# Voicecard-SVF-v06.net
KiCad netlist of a schematic drawn in EAGLE
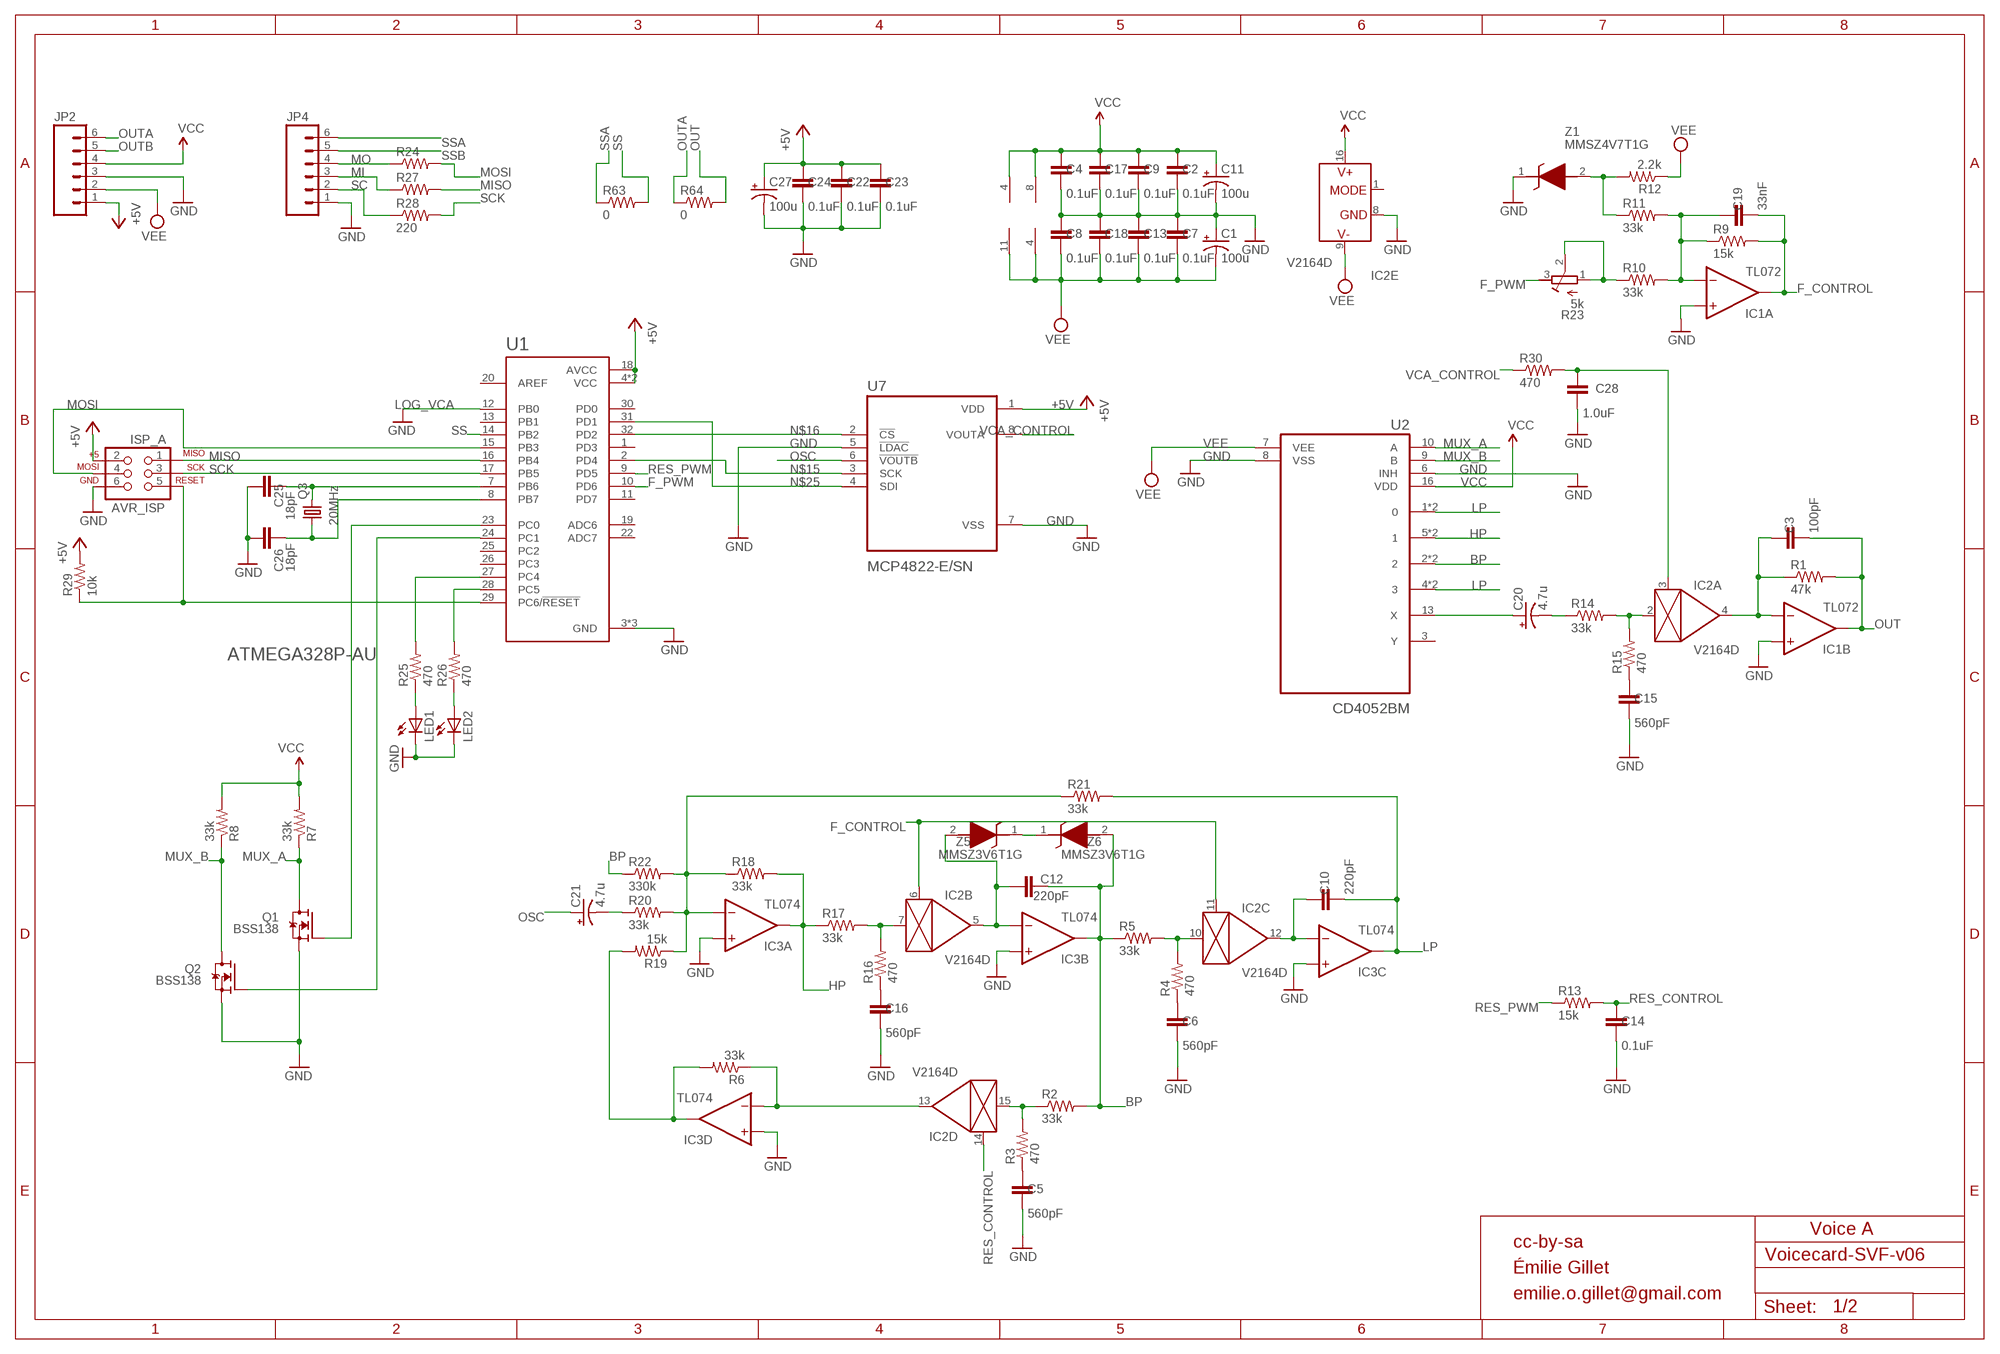
[diagram p0: schematic, sheet 1]
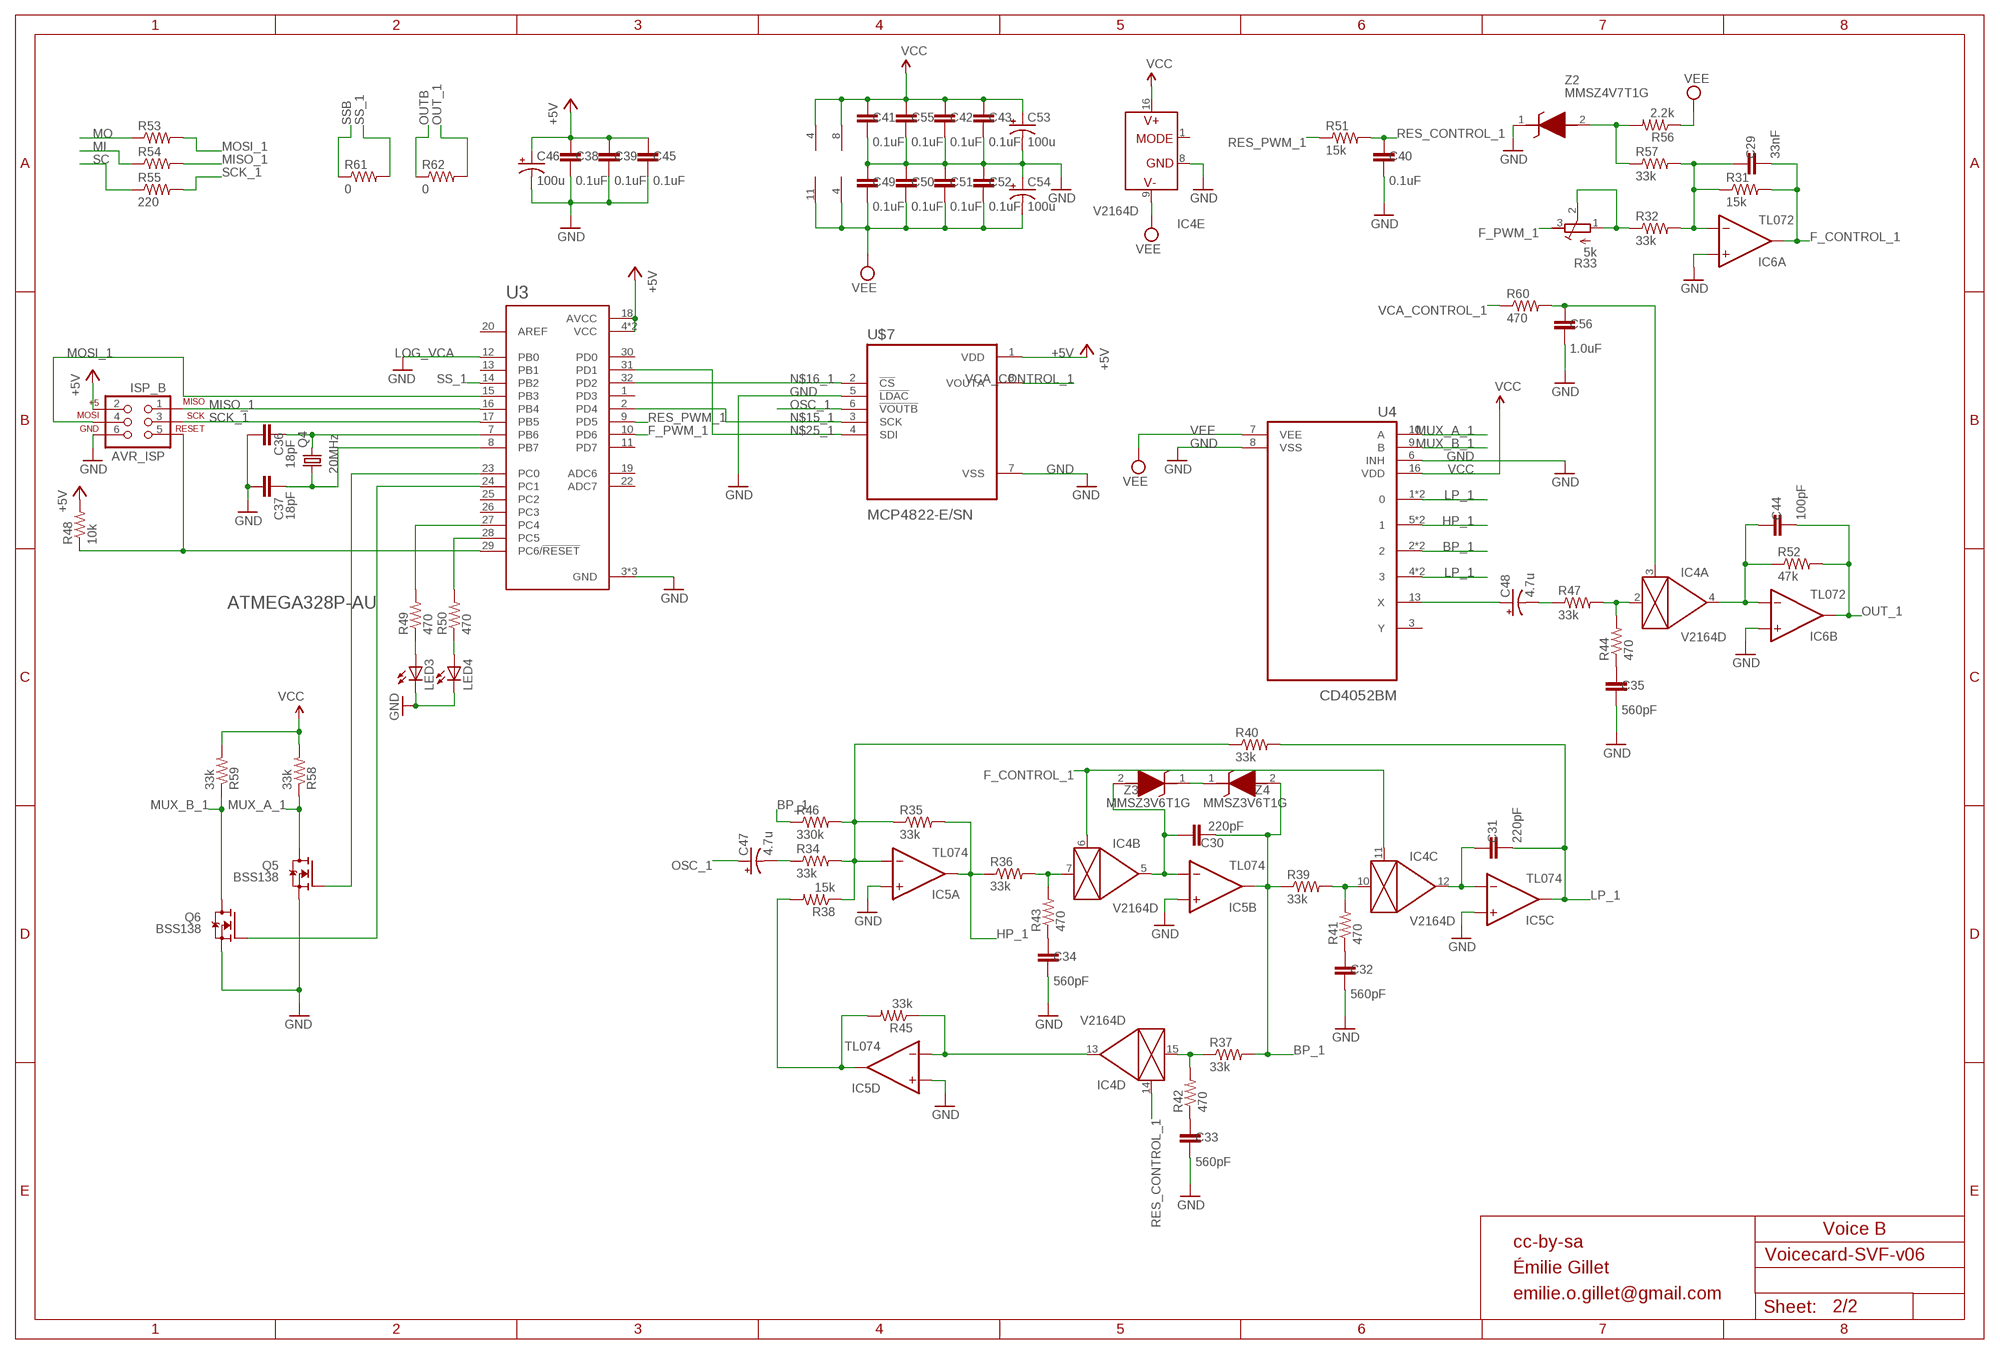
[diagram p1: schematic, sheet 2]

(export (version "E")
  (design (tool "Eeschema 10.0.6"))
  (components
    (comp (ref "C1")
      (value "100u")
      (footprint "eagle-import:PANASONIC_C")
      (libsource (lib "eagle-import") (part "CPOL-USC"))
    )
    (comp (ref "C2")
      (value "0.1uF")
      (footprint "eagle-import:0603")
      (libsource (lib "eagle-import") (part "0.1UF-0603-25V-5%"))
    )
    (comp (ref "C3")
      (value "100pF")
      (footprint "eagle-import:0603")
      (libsource (lib "eagle-import") (part "100PF-0603-50V-5%"))
    )
    (comp (ref "C4")
      (value "0.1uF")
      (footprint "eagle-import:0603")
      (libsource (lib "eagle-import") (part "0.1UF-0603-25V-5%"))
    )
    (comp (ref "C5")
      (value "560pF")
      (footprint "eagle-import:0603")
      (libsource (lib "eagle-import") (part "560PF-0603-50V-5%"))
    )
    (comp (ref "C6")
      (value "560pF")
      (footprint "eagle-import:0603")
      (libsource (lib "eagle-import") (part "560PF-0603-50V-5%"))
    )
    (comp (ref "C7")
      (value "0.1uF")
      (footprint "eagle-import:0603")
      (libsource (lib "eagle-import") (part "0.1UF-0603-25V-5%"))
    )
    (comp (ref "C8")
      (value "0.1uF")
      (footprint "eagle-import:0603")
      (libsource (lib "eagle-import") (part "0.1UF-0603-25V-5%"))
    )
    (comp (ref "C9")
      (value "0.1uF")
      (footprint "eagle-import:0603")
      (libsource (lib "eagle-import") (part "0.1UF-0603-25V-5%"))
    )
    (comp (ref "C10")
      (value "220pF")
      (footprint "eagle-import:0603")
      (libsource (lib "eagle-import") (part "270PF-0603-50V-5%"))
    )
    (comp (ref "C11")
      (value "100u")
      (footprint "eagle-import:PANASONIC_C")
      (libsource (lib "eagle-import") (part "CPOL-USC"))
    )
    (comp (ref "C12")
      (value "220pF")
      (footprint "eagle-import:0603")
      (libsource (lib "eagle-import") (part "270PF-0603-50V-5%"))
    )
    (comp (ref "C13")
      (value "0.1uF")
      (footprint "eagle-import:0603")
      (libsource (lib "eagle-import") (part "0.1UF-0603-25V-5%"))
    )
    (comp (ref "C14")
      (value "0.1uF")
      (footprint "eagle-import:0603")
      (libsource (lib "eagle-import") (part "0.1UF-0603-25V-5%"))
    )
    (comp (ref "C15")
      (value "560pF")
      (footprint "eagle-import:0603")
      (libsource (lib "eagle-import") (part "560PF-0603-50V-5%"))
    )
    (comp (ref "C16")
      (value "560pF")
      (footprint "eagle-import:0603")
      (libsource (lib "eagle-import") (part "560PF-0603-50V-5%"))
    )
    (comp (ref "C17")
      (value "0.1uF")
      (footprint "eagle-import:0603")
      (libsource (lib "eagle-import") (part "0.1UF-0603-25V-5%"))
    )
    (comp (ref "C18")
      (value "0.1uF")
      (footprint "eagle-import:0603")
      (libsource (lib "eagle-import") (part "0.1UF-0603-25V-5%"))
    )
    (comp (ref "C19")
      (value "33nF")
      (footprint "eagle-import:0603")
      (libsource (lib "eagle-import") (part "33NF-0603-50V-10%"))
    )
    (comp (ref "C20")
      (value "4.7u")
      (footprint "eagle-import:PANASONIC_A")
      (libsource (lib "eagle-import") (part "CPOL-USA"))
    )
    (comp (ref "C21")
      (value "4.7u")
      (footprint "eagle-import:PANASONIC_A")
      (libsource (lib "eagle-import") (part "CPOL-USA"))
    )
    (comp (ref "C22")
      (value "0.1uF")
      (footprint "eagle-import:0603")
      (libsource (lib "eagle-import") (part "0.1UF-0603-25V-5%"))
    )
    (comp (ref "C23")
      (value "0.1uF")
      (footprint "eagle-import:0603")
      (libsource (lib "eagle-import") (part "0.1UF-0603-25V-5%"))
    )
    (comp (ref "C24")
      (value "0.1uF")
      (footprint "eagle-import:0603")
      (libsource (lib "eagle-import") (part "0.1UF-0603-25V-5%"))
    )
    (comp (ref "C25")
      (value "18pF")
      (footprint "eagle-import:0603")
      (libsource (lib "eagle-import") (part "18PF-0603-50V-5%"))
    )
    (comp (ref "C26")
      (value "18pF")
      (footprint "eagle-import:0603")
      (libsource (lib "eagle-import") (part "18PF-0603-50V-5%"))
    )
    (comp (ref "C27")
      (value "100u")
      (footprint "eagle-import:PANASONIC_C")
      (libsource (lib "eagle-import") (part "CPOL-USC"))
    )
    (comp (ref "C28")
      (value "1.0uF")
      (footprint "eagle-import:0603")
      (libsource (lib "eagle-import") (part "1.0UF-0603-16V-10%"))
    )
    (comp (ref "IC1")
      (value "TL072")
      (footprint "eagle-import:SO08")
      (libsource (lib "eagle-import") (part "TL072_SMD"))
    )
    (comp (ref "IC2")
      (value "V2164D")
      (footprint "eagle-import:SOIC16N")
      (libsource (lib "eagle-import") (part "SSM2164S"))
    )
    (comp (ref "IC3")
      (value "TL074")
      (footprint "eagle-import:SO14")
      (libsource (lib "eagle-import") (part "TL074_SMD"))
    )
    (comp (ref "ISP_A")
      (value "AVR_ISP")
      (footprint "eagle-import:2X3")
      (libsource (lib "eagle-import") (part "AVR_SPI_PRG_6PTH"))
    )
    (comp (ref "JP2")
      (value "M06SIP")
      (footprint "eagle-import:1X06")
      (libsource (lib "eagle-import") (part "M06SIP"))
    )
    (comp (ref "JP4")
      (value "M06SIP")
      (footprint "eagle-import:1X06")
      (libsource (lib "eagle-import") (part "M06SIP"))
    )
    (comp (ref "LED1")
      (value "LED3MM")
      (footprint "eagle-import:LED3MM")
      (libsource (lib "eagle-import") (part "LED3MM"))
    )
    (comp (ref "LED2")
      (value "LED3MM")
      (footprint "eagle-import:LED3MM")
      (libsource (lib "eagle-import") (part "LED3MM"))
    )
    (comp (ref "Q1")
      (value "BSS138")
      (footprint "eagle-import:SOT95P240X111-3N")
      (fields (field (name "MF") "ON Semiconductor"))
      (libsource (lib "eagle-import") (part "BSS138"))
    )
    (comp (ref "Q2")
      (value "BSS138")
      (footprint "eagle-import:SOT95P240X111-3N")
      (fields (field (name "MF") "ON Semiconductor"))
      (libsource (lib "eagle-import") (part "BSS138"))
    )
    (comp (ref "Q3")
      (value "20MHz")
      (footprint "eagle-import:HC49UP")
      (libsource (lib "eagle-import") (part "CRYSTALHC49UP"))
    )
    (comp (ref "R1")
      (value "47k")
      (footprint "eagle-import:0603")
      (libsource (lib "eagle-import") (part "47KOHM-0603-1/10W-1%"))
    )
    (comp (ref "R2")
      (value "33k")
      (footprint "eagle-import:0603")
      (libsource (lib "eagle-import") (part "33KOHM-0603-1/10W-1%"))
    )
    (comp (ref "R3")
      (value "470")
      (footprint "eagle-import:0603")
      (libsource (lib "eagle-import") (part "470OHM-0603-1/10W-1%"))
    )
    (comp (ref "R4")
      (value "470")
      (footprint "eagle-import:0603")
      (libsource (lib "eagle-import") (part "470OHM-0603-1/10W-1%"))
    )
    (comp (ref "R5")
      (value "33k")
      (footprint "eagle-import:0603")
      (libsource (lib "eagle-import") (part "33KOHM-0603-1/10W-1%"))
    )
    (comp (ref "R6")
      (value "33k")
      (footprint "eagle-import:0603")
      (libsource (lib "eagle-import") (part "33KOHM-0603-1/10W-1%"))
    )
    (comp (ref "R7")
      (value "33k")
      (footprint "eagle-import:0603")
      (libsource (lib "eagle-import") (part "33KOHM-0603-1/10W-1%"))
    )
    (comp (ref "R8")
      (value "33k")
      (footprint "eagle-import:0603")
      (libsource (lib "eagle-import") (part "33KOHM-0603-1/10W-1%"))
    )
    (comp (ref "R9")
      (value "15k")
      (footprint "eagle-import:0603")
      (libsource (lib "eagle-import") (part "15KOHM-0603-1/10W-1%"))
    )
    (comp (ref "R10")
      (value "33k")
      (footprint "eagle-import:0603")
      (libsource (lib "eagle-import") (part "33KOHM-0603-1/10W-1%"))
    )
    (comp (ref "R11")
      (value "33k")
      (footprint "eagle-import:0603")
      (libsource (lib "eagle-import") (part "33KOHM-0603-1/10W-1%"))
    )
    (comp (ref "R12")
      (value "2.2k")
      (footprint "eagle-import:0603")
      (libsource (lib "eagle-import") (part "2.2KOHM-0603-1/10W-1%"))
    )
    (comp (ref "R13")
      (value "15k")
      (footprint "eagle-import:0603")
      (libsource (lib "eagle-import") (part "15KOHM-0603-1/10W-1%"))
    )
    (comp (ref "R14")
      (value "33k")
      (footprint "eagle-import:0603")
      (libsource (lib "eagle-import") (part "33KOHM-0603-1/10W-1%"))
    )
    (comp (ref "R15")
      (value "470")
      (footprint "eagle-import:0603")
      (libsource (lib "eagle-import") (part "470OHM-0603-1/10W-1%"))
    )
    (comp (ref "R16")
      (value "470")
      (footprint "eagle-import:0603")
      (libsource (lib "eagle-import") (part "470OHM-0603-1/10W-1%"))
    )
    (comp (ref "R17")
      (value "33k")
      (footprint "eagle-import:0603")
      (libsource (lib "eagle-import") (part "33KOHM-0603-1/10W-1%"))
    )
    (comp (ref "R18")
      (value "33k")
      (footprint "eagle-import:0603")
      (libsource (lib "eagle-import") (part "33KOHM-0603-1/10W-1%"))
    )
    (comp (ref "R19")
      (value "15k")
      (footprint "eagle-import:0603")
      (libsource (lib "eagle-import") (part "15KOHM-0603-1/10W-1%"))
    )
    (comp (ref "R20")
      (value "33k")
      (footprint "eagle-import:0603")
      (libsource (lib "eagle-import") (part "33KOHM-0603-1/10W-1%"))
    )
    (comp (ref "R21")
      (value "33k")
      (footprint "eagle-import:0603")
      (libsource (lib "eagle-import") (part "33KOHM-0603-1/10W-1%"))
    )
    (comp (ref "R22")
      (value "330k")
      (footprint "eagle-import:0603")
      (libsource (lib "eagle-import") (part "330KOHM-0603-1/10W-1%"))
    )
    (comp (ref "R23")
      (value "5k")
      (footprint "eagle-import:RTRIM3296P")
      (libsource (lib "eagle-import") (part "R-TRIMM3296P"))
    )
    (comp (ref "R24")
      (value "220")
      (footprint "eagle-import:0603")
      (libsource (lib "eagle-import") (part "220OHM-0603-1/10W-1%"))
    )
    (comp (ref "R25")
      (value "470")
      (footprint "eagle-import:0603")
      (libsource (lib "eagle-import") (part "470OHM-0603-1/10W-1%"))
    )
    (comp (ref "R26")
      (value "470")
      (footprint "eagle-import:0603")
      (libsource (lib "eagle-import") (part "470OHM-0603-1/10W-1%"))
    )
    (comp (ref "R27")
      (value "220")
      (footprint "eagle-import:0603")
      (libsource (lib "eagle-import") (part "220OHM-0603-1/10W-1%"))
    )
    (comp (ref "R28")
      (value "220")
      (footprint "eagle-import:0603")
      (libsource (lib "eagle-import") (part "220OHM-0603-1/10W-1%"))
    )
    (comp (ref "R29")
      (value "10k")
      (footprint "eagle-import:0603")
      (libsource (lib "eagle-import") (part "10KOHM-0603-1/10W-1%"))
    )
    (comp (ref "R30")
      (value "470")
      (footprint "eagle-import:0603")
      (libsource (lib "eagle-import") (part "470OHM-0603-1/10W-1%"))
    )
    (comp (ref "R63")
      (value "0")
      (footprint "eagle-import:0603")
      (libsource (lib "eagle-import") (part "220OHM-0603-1/10W-1%"))
    )
    (comp (ref "R64")
      (value "0")
      (footprint "eagle-import:0603")
      (libsource (lib "eagle-import") (part "220OHM-0603-1/10W-1%"))
    )
    (comp (ref "U1")
      (value "ATMEGA328P-AU")
      (footprint "eagle-import:QFP80P900X900X120-32N")
      (fields (field (name "MF") "Microchip Technology"))
      (libsource (lib "eagle-import") (part "ATMEGA328P-AU"))
    )
    (comp (ref "U2")
      (value "CD4052BM")
      (footprint "eagle-import:SOIC127P600X175-16N")
      (fields (field (name "MF") "Texas Instruments"))
      (libsource (lib "eagle-import") (part "CD4052BM"))
    )
    (comp (ref "U7")
      (value "MCP4822-E/SN")
      (footprint "eagle-import:SOIC127P599X175-8N")
      (fields (field (name "MF") "Microchip"))
      (libsource (lib "eagle-import") (part "MCP4822-E/SN"))
    )
    (comp (ref "Z1")
      (value "MMSZ4V7T1G")
      (footprint "eagle-import:SOD3716X135N")
      (fields (field (name "MOUSER_PART_NUMBER") "863-MMSZ4V7T1G"))
      (libsource (lib "eagle-import") (part "MMSZ4V7T1G"))
    )
    (comp (ref "Z5")
      (value "MMSZ3V6T1G")
      (footprint "eagle-import:SOD3716X135N")
      (fields (field (name "MOUSER_PART_NUMBER") "863-MMSZ3V6T1G"))
      (libsource (lib "eagle-import") (part "MMSZ3V6T1G"))
    )
    (comp (ref "Z6")
      (value "MMSZ3V6T1G")
      (footprint "eagle-import:SOD3716X135N")
      (fields (field (name "MOUSER_PART_NUMBER") "863-MMSZ3V6T1G"))
      (libsource (lib "eagle-import") (part "MMSZ3V6T1G"))
    )
    (comp (ref "C29")
      (value "33nF")
      (footprint "eagle-import:0603")
      (libsource (lib "eagle-import") (part "33NF-0603-50V-10%"))
    )
    (comp (ref "C30")
      (value "220pF")
      (footprint "eagle-import:0603")
      (libsource (lib "eagle-import") (part "270PF-0603-50V-5%"))
    )
    (comp (ref "C31")
      (value "220pF")
      (footprint "eagle-import:0603")
      (libsource (lib "eagle-import") (part "270PF-0603-50V-5%"))
    )
    (comp (ref "C32")
      (value "560pF")
      (footprint "eagle-import:0603")
      (libsource (lib "eagle-import") (part "560PF-0603-50V-5%"))
    )
    (comp (ref "C33")
      (value "560pF")
      (footprint "eagle-import:0603")
      (libsource (lib "eagle-import") (part "560PF-0603-50V-5%"))
    )
    (comp (ref "C34")
      (value "560pF")
      (footprint "eagle-import:0603")
      (libsource (lib "eagle-import") (part "560PF-0603-50V-5%"))
    )
    (comp (ref "C35")
      (value "560pF")
      (footprint "eagle-import:0603")
      (libsource (lib "eagle-import") (part "560PF-0603-50V-5%"))
    )
    (comp (ref "C36")
      (value "18pF")
      (footprint "eagle-import:0603")
      (libsource (lib "eagle-import") (part "18PF-0603-50V-5%"))
    )
    (comp (ref "C37")
      (value "18pF")
      (footprint "eagle-import:0603")
      (libsource (lib "eagle-import") (part "18PF-0603-50V-5%"))
    )
    (comp (ref "C38")
      (value "0.1uF")
      (footprint "eagle-import:0603")
      (libsource (lib "eagle-import") (part "0.1UF-0603-25V-5%"))
    )
    (comp (ref "C39")
      (value "0.1uF")
      (footprint "eagle-import:0603")
      (libsource (lib "eagle-import") (part "0.1UF-0603-25V-5%"))
    )
    (comp (ref "C40")
      (value "0.1uF")
      (footprint "eagle-import:0603")
      (libsource (lib "eagle-import") (part "0.1UF-0603-25V-5%"))
    )
    (comp (ref "C41")
      (value "0.1uF")
      (footprint "eagle-import:0603")
      (libsource (lib "eagle-import") (part "0.1UF-0603-25V-5%"))
    )
    (comp (ref "C42")
      (value "0.1uF")
      (footprint "eagle-import:0603")
      (libsource (lib "eagle-import") (part "0.1UF-0603-25V-5%"))
    )
    (comp (ref "C43")
      (value "0.1uF")
      (footprint "eagle-import:0603")
      (libsource (lib "eagle-import") (part "0.1UF-0603-25V-5%"))
    )
    (comp (ref "C44")
      (value "100pF")
      (footprint "eagle-import:0603")
      (libsource (lib "eagle-import") (part "100PF-0603-50V-5%"))
    )
    (comp (ref "C45")
      (value "0.1uF")
      (footprint "eagle-import:0603")
      (libsource (lib "eagle-import") (part "0.1UF-0603-25V-5%"))
    )
    (comp (ref "C46")
      (value "100u")
      (footprint "eagle-import:PANASONIC_C")
      (libsource (lib "eagle-import") (part "CPOL-USC"))
    )
    (comp (ref "C47")
      (value "4.7u")
      (footprint "eagle-import:PANASONIC_A")
      (libsource (lib "eagle-import") (part "CPOL-USA"))
    )
    (comp (ref "C48")
      (value "4.7u")
      (footprint "eagle-import:PANASONIC_A")
      (libsource (lib "eagle-import") (part "CPOL-USA"))
    )
    (comp (ref "C49")
      (value "0.1uF")
      (footprint "eagle-import:0603")
      (libsource (lib "eagle-import") (part "0.1UF-0603-25V-5%"))
    )
    (comp (ref "C50")
      (value "0.1uF")
      (footprint "eagle-import:0603")
      (libsource (lib "eagle-import") (part "0.1UF-0603-25V-5%"))
    )
    (comp (ref "C51")
      (value "0.1uF")
      (footprint "eagle-import:0603")
      (libsource (lib "eagle-import") (part "0.1UF-0603-25V-5%"))
    )
    (comp (ref "C52")
      (value "0.1uF")
      (footprint "eagle-import:0603")
      (libsource (lib "eagle-import") (part "0.1UF-0603-25V-5%"))
    )
    (comp (ref "C53")
      (value "100u")
      (footprint "eagle-import:PANASONIC_C")
      (libsource (lib "eagle-import") (part "CPOL-USC"))
    )
    (comp (ref "C54")
      (value "100u")
      (footprint "eagle-import:PANASONIC_C")
      (libsource (lib "eagle-import") (part "CPOL-USC"))
    )
    (comp (ref "C55")
      (value "0.1uF")
      (footprint "eagle-import:0603")
      (libsource (lib "eagle-import") (part "0.1UF-0603-25V-5%"))
    )
    (comp (ref "C56")
      (value "1.0uF")
      (footprint "eagle-import:0603")
      (libsource (lib "eagle-import") (part "1.0UF-0603-16V-10%"))
    )
    (comp (ref "IC4")
      (value "V2164D")
      (footprint "eagle-import:SOIC16N")
      (libsource (lib "eagle-import") (part "SSM2164S"))
    )
    (comp (ref "IC5")
      (value "TL074")
      (footprint "eagle-import:SO14")
      (libsource (lib "eagle-import") (part "TL074_SMD"))
    )
    (comp (ref "IC6")
      (value "TL072")
      (footprint "eagle-import:SO08")
      (libsource (lib "eagle-import") (part "TL072_SMD"))
    )
    (comp (ref "ISP_B")
      (value "AVR_ISP")
      (footprint "eagle-import:2X3")
      (libsource (lib "eagle-import") (part "AVR_SPI_PRG_6PTH"))
    )
    (comp (ref "LED3")
      (value "LED3MM")
      (footprint "eagle-import:LED3MM")
      (libsource (lib "eagle-import") (part "LED3MM"))
    )
    (comp (ref "LED4")
      (value "LED3MM")
      (footprint "eagle-import:LED3MM")
      (libsource (lib "eagle-import") (part "LED3MM"))
    )
    (comp (ref "Q4")
      (value "20MHz")
      (footprint "eagle-import:HC49UP")
      (libsource (lib "eagle-import") (part "CRYSTALHC49UP"))
    )
    (comp (ref "Q5")
      (value "BSS138")
      (footprint "eagle-import:SOT95P240X111-3N")
      (fields (field (name "MF") "ON Semiconductor"))
      (libsource (lib "eagle-import") (part "BSS138"))
    )
    (comp (ref "Q6")
      (value "BSS138")
      (footprint "eagle-import:SOT95P240X111-3N")
      (fields (field (name "MF") "ON Semiconductor"))
      (libsource (lib "eagle-import") (part "BSS138"))
    )
    (comp (ref "R31")
      (value "15k")
      (footprint "eagle-import:0603")
      (libsource (lib "eagle-import") (part "15KOHM-0603-1/10W-1%"))
    )
    (comp (ref "R32")
      (value "33k")
      (footprint "eagle-import:0603")
      (libsource (lib "eagle-import") (part "33KOHM-0603-1/10W-1%"))
    )
    (comp (ref "R33")
      (value "5k")
      (footprint "eagle-import:RTRIM3296P")
      (libsource (lib "eagle-import") (part "R-TRIMM3296P"))
    )
    (comp (ref "R34")
      (value "33k")
      (footprint "eagle-import:0603")
      (libsource (lib "eagle-import") (part "33KOHM-0603-1/10W-1%"))
    )
    (comp (ref "R35")
      (value "33k")
      (footprint "eagle-import:0603")
      (libsource (lib "eagle-import") (part "33KOHM-0603-1/10W-1%"))
    )
    (comp (ref "R36")
      (value "33k")
      (footprint "eagle-import:0603")
      (libsource (lib "eagle-import") (part "33KOHM-0603-1/10W-1%"))
    )
    (comp (ref "R37")
      (value "33k")
      (footprint "eagle-import:0603")
      (libsource (lib "eagle-import") (part "33KOHM-0603-1/10W-1%"))
    )
    (comp (ref "R38")
      (value "15k")
      (footprint "eagle-import:0603")
      (libsource (lib "eagle-import") (part "15KOHM-0603-1/10W-1%"))
    )
    (comp (ref "R39")
      (value "33k")
      (footprint "eagle-import:0603")
      (libsource (lib "eagle-import") (part "33KOHM-0603-1/10W-1%"))
    )
    (comp (ref "R40")
      (value "33k")
      (footprint "eagle-import:0603")
      (libsource (lib "eagle-import") (part "33KOHM-0603-1/10W-1%"))
    )
    (comp (ref "R41")
      (value "470")
      (footprint "eagle-import:0603")
      (libsource (lib "eagle-import") (part "470OHM-0603-1/10W-1%"))
    )
    (comp (ref "R42")
      (value "470")
      (footprint "eagle-import:0603")
      (libsource (lib "eagle-import") (part "470OHM-0603-1/10W-1%"))
    )
    (comp (ref "R43")
      (value "470")
      (footprint "eagle-import:0603")
      (libsource (lib "eagle-import") (part "470OHM-0603-1/10W-1%"))
    )
    (comp (ref "R44")
      (value "470")
      (footprint "eagle-import:0603")
      (libsource (lib "eagle-import") (part "470OHM-0603-1/10W-1%"))
    )
    (comp (ref "R45")
      (value "33k")
      (footprint "eagle-import:0603")
      (libsource (lib "eagle-import") (part "33KOHM-0603-1/10W-1%"))
    )
    (comp (ref "R46")
      (value "330k")
      (footprint "eagle-import:0603")
      (libsource (lib "eagle-import") (part "330KOHM-0603-1/10W-1%"))
    )
    (comp (ref "R47")
      (value "33k")
      (footprint "eagle-import:0603")
      (libsource (lib "eagle-import") (part "33KOHM-0603-1/10W-1%"))
    )
    (comp (ref "R48")
      (value "10k")
      (footprint "eagle-import:0603")
      (libsource (lib "eagle-import") (part "10KOHM-0603-1/10W-1%"))
    )
    (comp (ref "R49")
      (value "470")
      (footprint "eagle-import:0603")
      (libsource (lib "eagle-import") (part "470OHM-0603-1/10W-1%"))
    )
    (comp (ref "R50")
      (value "470")
      (footprint "eagle-import:0603")
      (libsource (lib "eagle-import") (part "470OHM-0603-1/10W-1%"))
    )
    (comp (ref "R51")
      (value "15k")
      (footprint "eagle-import:0603")
      (libsource (lib "eagle-import") (part "15KOHM-0603-1/10W-1%"))
    )
    (comp (ref "R52")
      (value "47k")
      (footprint "eagle-import:0603")
      (libsource (lib "eagle-import") (part "47KOHM-0603-1/10W-1%"))
    )
    (comp (ref "R53")
      (value "220")
      (footprint "eagle-import:0603")
      (libsource (lib "eagle-import") (part "220OHM-0603-1/10W-1%"))
    )
    (comp (ref "R54")
      (value "220")
      (footprint "eagle-import:0603")
      (libsource (lib "eagle-import") (part "220OHM-0603-1/10W-1%"))
    )
    (comp (ref "R55")
      (value "220")
      (footprint "eagle-import:0603")
      (libsource (lib "eagle-import") (part "220OHM-0603-1/10W-1%"))
    )
    (comp (ref "R56")
      (value "2.2k")
      (footprint "eagle-import:0603")
      (libsource (lib "eagle-import") (part "2.2KOHM-0603-1/10W-1%"))
    )
    (comp (ref "R57")
      (value "33k")
      (footprint "eagle-import:0603")
      (libsource (lib "eagle-import") (part "33KOHM-0603-1/10W-1%"))
    )
    (comp (ref "R58")
      (value "33k")
      (footprint "eagle-import:0603")
      (libsource (lib "eagle-import") (part "33KOHM-0603-1/10W-1%"))
    )
    (comp (ref "R59")
      (value "33k")
      (footprint "eagle-import:0603")
      (libsource (lib "eagle-import") (part "33KOHM-0603-1/10W-1%"))
    )
    (comp (ref "R60")
      (value "470")
      (footprint "eagle-import:0603")
      (libsource (lib "eagle-import") (part "470OHM-0603-1/10W-1%"))
    )
    (comp (ref "R61")
      (value "0")
      (footprint "eagle-import:0603")
      (libsource (lib "eagle-import") (part "220OHM-0603-1/10W-1%"))
    )
    (comp (ref "R62")
      (value "0")
      (footprint "eagle-import:0603")
      (libsource (lib "eagle-import") (part "220OHM-0603-1/10W-1%"))
    )
    (comp (ref "U$7")
      (value "MCP4822-E/SN")
      (footprint "eagle-import:SOIC127P599X175-8N")
      (fields (field (name "MF") "Microchip"))
      (libsource (lib "eagle-import") (part "MCP4822-E/SN"))
    )
    (comp (ref "U3")
      (value "ATMEGA328P-AU")
      (footprint "eagle-import:QFP80P900X900X120-32N")
      (fields (field (name "MF") "Microchip Technology"))
      (libsource (lib "eagle-import") (part "ATMEGA328P-AU"))
    )
    (comp (ref "U4")
      (value "CD4052BM")
      (footprint "eagle-import:SOIC127P600X175-16N")
      (fields (field (name "MF") "Texas Instruments"))
      (libsource (lib "eagle-import") (part "CD4052BM"))
    )
    (comp (ref "Z2")
      (value "MMSZ4V7T1G")
      (footprint "eagle-import:SOD3716X135N")
      (fields (field (name "MOUSER_PART_NUMBER") "863-MMSZ4V7T1G"))
      (libsource (lib "eagle-import") (part "MMSZ4V7T1G"))
    )
    (comp (ref "Z3")
      (value "MMSZ3V6T1G")
      (footprint "eagle-import:SOD3716X135N")
      (fields (field (name "MOUSER_PART_NUMBER") "863-MMSZ3V6T1G"))
      (libsource (lib "eagle-import") (part "MMSZ3V6T1G"))
    )
    (comp (ref "Z4")
      (value "MMSZ3V6T1G")
      (footprint "eagle-import:SOD3716X135N")
      (fields (field (name "MOUSER_PART_NUMBER") "863-MMSZ3V6T1G"))
      (libsource (lib "eagle-import") (part "MMSZ3V6T1G"))
    )
  )
  (nets
    (net (code "1") (name "+5V") (class "Default")
      (node (ref "C22") (pin "1") (pinfunction "1_1") (pintype "passive"))
      (node (ref "C23") (pin "1") (pinfunction "1_1") (pintype "passive"))
      (node (ref "C24") (pin "1") (pinfunction "1_1") (pintype "passive"))
      (node (ref "C27") (pin "+") (pinfunction "+_+") (pintype "passive"))
      (node (ref "C38") (pin "1") (pinfunction "1_1") (pintype "passive"))
      (node (ref "C39") (pin "1") (pinfunction "1_1") (pintype "passive"))
      (node (ref "C45") (pin "1") (pinfunction "1_1") (pintype "passive"))
      (node (ref "C46") (pin "+") (pinfunction "+_+") (pintype "passive"))
      (node (ref "ISP_A") (pin "2") (pinfunction "2_2") (pintype "passive"))
      (node (ref "ISP_B") (pin "2") (pinfunction "2_2") (pintype "passive"))
      (node (ref "JP2") (pin "1") (pinfunction "1_1") (pintype "passive"))
      (node (ref "R29") (pin "2") (pinfunction "2_2") (pintype "passive"))
      (node (ref "R48") (pin "2") (pinfunction "2_2") (pintype "passive"))
      (node (ref "U$7") (pin "1") (pinfunction "VDD_1") (pintype "power_in"))
      (node (ref "U1") (pin "18") (pinfunction "AVCC_18") (pintype "power_in"))
      (node (ref "U1") (pin "4") (pinfunction "VCC_4") (pintype "power_in"))
      (node (ref "U1") (pin "6") (pinfunction "VCC_6") (pintype "power_in"))
      (node (ref "U3") (pin "18") (pinfunction "AVCC_18") (pintype "power_in"))
      (node (ref "U3") (pin "4") (pinfunction "VCC_4") (pintype "power_in"))
      (node (ref "U3") (pin "6") (pinfunction "VCC_6") (pintype "power_in"))
      (node (ref "U7") (pin "1") (pinfunction "VDD_1") (pintype "power_in"))
    )
    (net (code "2") (name "BP") (class "Default")
      (node (ref "C12") (pin "2") (pinfunction "2_2") (pintype "passive"))
      (node (ref "IC3") (pin "7") (pinfunction "OUT_7") (pintype "output"))
      (node (ref "R2") (pin "2") (pinfunction "2_2") (pintype "passive"))
      (node (ref "R22") (pin "1") (pinfunction "1_1") (pintype "passive"))
      (node (ref "R5") (pin "1") (pinfunction "1_1") (pintype "passive"))
      (node (ref "U2") (pin "15") (pinfunction "2_15") (pintype "bidirectional"))
      (node (ref "U2") (pin "2") (pinfunction "2_2") (pintype "bidirectional"))
      (node (ref "Z6") (pin "2") (pinfunction "A_2") (pintype "bidirectional"))
    )
    (net (code "3") (name "BP_1") (class "Default")
      (node (ref "C30") (pin "2") (pinfunction "2_2") (pintype "passive"))
      (node (ref "IC5") (pin "7") (pinfunction "OUT_7") (pintype "output"))
      (node (ref "R37") (pin "2") (pinfunction "2_2") (pintype "passive"))
      (node (ref "R39") (pin "1") (pinfunction "1_1") (pintype "passive"))
      (node (ref "R46") (pin "1") (pinfunction "1_1") (pintype "passive"))
      (node (ref "U4") (pin "15") (pinfunction "2_15") (pintype "bidirectional"))
      (node (ref "U4") (pin "2") (pinfunction "2_2") (pintype "bidirectional"))
      (node (ref "Z4") (pin "2") (pinfunction "A_2") (pintype "bidirectional"))
    )
    (net (code "4") (name "F_CONTROL") (class "Default")
      (node (ref "C19") (pin "2") (pinfunction "2_2") (pintype "passive"))
      (node (ref "IC1") (pin "1") (pinfunction "OUT_1") (pintype "output"))
      (node (ref "IC2") (pin "11") (pinfunction "CTRL_11") (pintype "input"))
      (node (ref "IC2") (pin "6") (pinfunction "CTRL_6") (pintype "input"))
      (node (ref "R9") (pin "2") (pinfunction "2_2") (pintype "passive"))
    )
    (net (code "5") (name "F_CONTROL_1") (class "Default")
      (node (ref "C29") (pin "2") (pinfunction "2_2") (pintype "passive"))
      (node (ref "IC4") (pin "11") (pinfunction "CTRL_11") (pintype "input"))
      (node (ref "IC4") (pin "6") (pinfunction "CTRL_6") (pintype "input"))
      (node (ref "IC6") (pin "1") (pinfunction "OUT_1") (pintype "output"))
      (node (ref "R31") (pin "2") (pinfunction "2_2") (pintype "passive"))
    )
    (net (code "6") (name "F_PWM") (class "Default")
      (node (ref "R23") (pin "3") (pinfunction "A_3") (pintype "passive"))
      (node (ref "U1") (pin "10") (pinfunction "PD6_10") (pintype "bidirectional"))
    )
    (net (code "7") (name "F_PWM_1") (class "Default")
      (node (ref "R33") (pin "3") (pinfunction "A_3") (pintype "passive"))
      (node (ref "U3") (pin "10") (pinfunction "PD6_10") (pintype "bidirectional"))
    )
    (net (code "8") (name "GND") (class "Default")
      (node (ref "C1") (pin "+") (pinfunction "+_+") (pintype "passive"))
      (node (ref "C11") (pin "-") (pinfunction "-_-") (pintype "passive"))
      (node (ref "C13") (pin "1") (pinfunction "1_1") (pintype "passive"))
      (node (ref "C14") (pin "2") (pinfunction "2_2") (pintype "passive"))
      (node (ref "C15") (pin "2") (pinfunction "2_2") (pintype "passive"))
      (node (ref "C16") (pin "2") (pinfunction "2_2") (pintype "passive"))
      (node (ref "C17") (pin "2") (pinfunction "2_2") (pintype "passive"))
      (node (ref "C18") (pin "1") (pinfunction "1_1") (pintype "passive"))
      (node (ref "C2") (pin "2") (pinfunction "2_2") (pintype "passive"))
      (node (ref "C22") (pin "2") (pinfunction "2_2") (pintype "passive"))
      (node (ref "C23") (pin "2") (pinfunction "2_2") (pintype "passive"))
      (node (ref "C24") (pin "2") (pinfunction "2_2") (pintype "passive"))
      (node (ref "C25") (pin "1") (pinfunction "1_1") (pintype "passive"))
      (node (ref "C26") (pin "1") (pinfunction "1_1") (pintype "passive"))
      (node (ref "C27") (pin "-") (pinfunction "-_-") (pintype "passive"))
      (node (ref "C28") (pin "2") (pinfunction "2_2") (pintype "passive"))
      (node (ref "C32") (pin "2") (pinfunction "2_2") (pintype "passive"))
      (node (ref "C33") (pin "2") (pinfunction "2_2") (pintype "passive"))
      (node (ref "C34") (pin "2") (pinfunction "2_2") (pintype "passive"))
      (node (ref "C35") (pin "2") (pinfunction "2_2") (pintype "passive"))
      (node (ref "C36") (pin "1") (pinfunction "1_1") (pintype "passive"))
      (node (ref "C37") (pin "1") (pinfunction "1_1") (pintype "passive"))
      (node (ref "C38") (pin "2") (pinfunction "2_2") (pintype "passive"))
      (node (ref "C39") (pin "2") (pinfunction "2_2") (pintype "passive"))
      (node (ref "C4") (pin "2") (pinfunction "2_2") (pintype "passive"))
      (node (ref "C40") (pin "2") (pinfunction "2_2") (pintype "passive"))
      (node (ref "C41") (pin "2") (pinfunction "2_2") (pintype "passive"))
      (node (ref "C42") (pin "2") (pinfunction "2_2") (pintype "passive"))
      (node (ref "C43") (pin "2") (pinfunction "2_2") (pintype "passive"))
      (node (ref "C45") (pin "2") (pinfunction "2_2") (pintype "passive"))
      (node (ref "C46") (pin "-") (pinfunction "-_-") (pintype "passive"))
      (node (ref "C49") (pin "1") (pinfunction "1_1") (pintype "passive"))
      (node (ref "C5") (pin "2") (pinfunction "2_2") (pintype "passive"))
      (node (ref "C50") (pin "1") (pinfunction "1_1") (pintype "passive"))
      (node (ref "C51") (pin "1") (pinfunction "1_1") (pintype "passive"))
      (node (ref "C52") (pin "1") (pinfunction "1_1") (pintype "passive"))
      (node (ref "C53") (pin "-") (pinfunction "-_-") (pintype "passive"))
      (node (ref "C54") (pin "+") (pinfunction "+_+") (pintype "passive"))
      (node (ref "C55") (pin "2") (pinfunction "2_2") (pintype "passive"))
      (node (ref "C56") (pin "2") (pinfunction "2_2") (pintype "passive"))
      (node (ref "C6") (pin "2") (pinfunction "2_2") (pintype "passive"))
      (node (ref "C7") (pin "1") (pinfunction "1_1") (pintype "passive"))
      (node (ref "C8") (pin "1") (pinfunction "1_1") (pintype "passive"))
      (node (ref "C9") (pin "2") (pinfunction "2_2") (pintype "passive"))
      (node (ref "IC1") (pin "3") (pinfunction "+IN_3") (pintype "input"))
      (node (ref "IC1") (pin "5") (pinfunction "+IN_5") (pintype "input"))
      (node (ref "IC2") (pin "8") (pinfunction "GND_8") (pintype "power_in"))
      (node (ref "IC3") (pin "10") (pinfunction "+IN_10") (pintype "input"))
      (node (ref "IC3") (pin "12") (pinfunction "+IN_12") (pintype "input"))
      (node (ref "IC3") (pin "3") (pinfunction "+IN_3") (pintype "input"))
      (node (ref "IC3") (pin "5") (pinfunction "+IN_5") (pintype "input"))
      (node (ref "IC4") (pin "8") (pinfunction "GND_8") (pintype "power_in"))
      (node (ref "IC5") (pin "10") (pinfunction "+IN_10") (pintype "input"))
      (node (ref "IC5") (pin "12") (pinfunction "+IN_12") (pintype "input"))
      (node (ref "IC5") (pin "3") (pinfunction "+IN_3") (pintype "input"))
      (node (ref "IC5") (pin "5") (pinfunction "+IN_5") (pintype "input"))
      (node (ref "IC6") (pin "3") (pinfunction "+IN_3") (pintype "input"))
      (node (ref "IC6") (pin "5") (pinfunction "+IN_5") (pintype "input"))
      (node (ref "ISP_A") (pin "6") (pinfunction "6_6") (pintype "passive"))
      (node (ref "ISP_B") (pin "6") (pinfunction "6_6") (pintype "passive"))
      (node (ref "JP2") (pin "3") (pinfunction "3_3") (pintype "passive"))
      (node (ref "JP4") (pin "1") (pinfunction "1_1") (pintype "passive"))
      (node (ref "LED1") (pin "K") (pinfunction "C_K") (pintype "passive"))
      (node (ref "LED2") (pin "K") (pinfunction "C_K") (pintype "passive"))
      (node (ref "LED3") (pin "K") (pinfunction "C_K") (pintype "passive"))
      (node (ref "LED4") (pin "K") (pinfunction "C_K") (pintype "passive"))
      (node (ref "Q1") (pin "2") (pinfunction "S_2") (pintype "passive"))
      (node (ref "Q2") (pin "2") (pinfunction "S_2") (pintype "passive"))
      (node (ref "Q5") (pin "2") (pinfunction "S_2") (pintype "passive"))
      (node (ref "Q6") (pin "2") (pinfunction "S_2") (pintype "passive"))
      (node (ref "U$7") (pin "5") (pinfunction "~{LDAC}_5") (pintype "input"))
      (node (ref "U$7") (pin "7") (pinfunction "VSS_7") (pintype "power_in"))
      (node (ref "U1") (pin "12") (pinfunction "PB0_12") (pintype "bidirectional"))
      (node (ref "U1") (pin "21") (pinfunction "GND_21") (pintype "power_in"))
      (node (ref "U1") (pin "3") (pinfunction "GND_3") (pintype "power_in"))
      (node (ref "U1") (pin "5") (pinfunction "GND_5") (pintype "power_in"))
      (node (ref "U2") (pin "6") (pinfunction "INH_6") (pintype "input"))
      (node (ref "U2") (pin "8") (pinfunction "VSS_8") (pintype "power_in"))
      (node (ref "U3") (pin "12") (pinfunction "PB0_12") (pintype "bidirectional"))
      (node (ref "U3") (pin "21") (pinfunction "GND_21") (pintype "power_in"))
      (node (ref "U3") (pin "3") (pinfunction "GND_3") (pintype "power_in"))
      (node (ref "U3") (pin "5") (pinfunction "GND_5") (pintype "power_in"))
      (node (ref "U4") (pin "6") (pinfunction "INH_6") (pintype "input"))
      (node (ref "U4") (pin "8") (pinfunction "VSS_8") (pintype "power_in"))
      (node (ref "U7") (pin "5") (pinfunction "~{LDAC}_5") (pintype "input"))
      (node (ref "U7") (pin "7") (pinfunction "VSS_7") (pintype "power_in"))
      (node (ref "Z1") (pin "1") (pinfunction "K_1") (pintype "bidirectional"))
      (node (ref "Z2") (pin "1") (pinfunction "K_1") (pintype "bidirectional"))
    )
    (net (code "9") (name "HP") (class "Default")
      (node (ref "IC3") (pin "1") (pinfunction "OUT_1") (pintype "output"))
      (node (ref "R17") (pin "1") (pinfunction "1_1") (pintype "passive"))
      (node (ref "R18") (pin "2") (pinfunction "2_2") (pintype "passive"))
      (node (ref "U2") (pin "14") (pinfunction "1_14") (pintype "bidirectional"))
      (node (ref "U2") (pin "5") (pinfunction "1_5") (pintype "bidirectional"))
    )
    (net (code "10") (name "HP_1") (class "Default")
      (node (ref "IC5") (pin "1") (pinfunction "OUT_1") (pintype "output"))
      (node (ref "R35") (pin "2") (pinfunction "2_2") (pintype "passive"))
      (node (ref "R36") (pin "1") (pinfunction "1_1") (pintype "passive"))
      (node (ref "U4") (pin "14") (pinfunction "1_14") (pintype "bidirectional"))
      (node (ref "U4") (pin "5") (pinfunction "1_5") (pintype "bidirectional"))
    )
    (net (code "11") (name "LP") (class "Default")
      (node (ref "C10") (pin "2") (pinfunction "2_2") (pintype "passive"))
      (node (ref "IC3") (pin "8") (pinfunction "OUT_8") (pintype "output"))
      (node (ref "R21") (pin "2") (pinfunction "2_2") (pintype "passive"))
      (node (ref "U2") (pin "1") (pinfunction "0_1") (pintype "bidirectional"))
      (node (ref "U2") (pin "11") (pinfunction "3_11") (pintype "bidirectional"))
      (node (ref "U2") (pin "12") (pinfunction "0_12") (pintype "bidirectional"))
      (node (ref "U2") (pin "4") (pinfunction "3_4") (pintype "bidirectional"))
    )
    (net (code "12") (name "LP_1") (class "Default")
      (node (ref "C31") (pin "2") (pinfunction "2_2") (pintype "passive"))
      (node (ref "IC5") (pin "8") (pinfunction "OUT_8") (pintype "output"))
      (node (ref "R40") (pin "2") (pinfunction "2_2") (pintype "passive"))
      (node (ref "U4") (pin "1") (pinfunction "0_1") (pintype "bidirectional"))
      (node (ref "U4") (pin "11") (pinfunction "3_11") (pintype "bidirectional"))
      (node (ref "U4") (pin "12") (pinfunction "0_12") (pintype "bidirectional"))
      (node (ref "U4") (pin "4") (pinfunction "3_4") (pintype "bidirectional"))
    )
    (net (code "13") (name "MI") (class "Default")
      (node (ref "JP4") (pin "3") (pinfunction "3_3") (pintype "passive"))
      (node (ref "R27") (pin "1") (pinfunction "1_1") (pintype "passive"))
      (node (ref "R54") (pin "1") (pinfunction "1_1") (pintype "passive"))
    )
    (net (code "14") (name "MISO") (class "Default")
      (node (ref "ISP_A") (pin "1") (pinfunction "1_1") (pintype "passive"))
      (node (ref "R27") (pin "2") (pinfunction "2_2") (pintype "passive"))
      (node (ref "U1") (pin "16") (pinfunction "PB4_16") (pintype "bidirectional"))
    )
    (net (code "15") (name "MISO_1") (class "Default")
      (node (ref "ISP_B") (pin "1") (pinfunction "1_1") (pintype "passive"))
      (node (ref "R54") (pin "2") (pinfunction "2_2") (pintype "passive"))
      (node (ref "U3") (pin "16") (pinfunction "PB4_16") (pintype "bidirectional"))
    )
    (net (code "16") (name "MO") (class "Default")
      (node (ref "JP4") (pin "4") (pinfunction "4_4") (pintype "passive"))
      (node (ref "R24") (pin "1") (pinfunction "1_1") (pintype "passive"))
      (node (ref "R53") (pin "1") (pinfunction "1_1") (pintype "passive"))
    )
    (net (code "17") (name "MOSI") (class "Default")
      (node (ref "ISP_A") (pin "4") (pinfunction "4_4") (pintype "passive"))
      (node (ref "R24") (pin "2") (pinfunction "2_2") (pintype "passive"))
      (node (ref "U1") (pin "15") (pinfunction "PB3_15") (pintype "bidirectional"))
    )
    (net (code "18") (name "MOSI_1") (class "Default")
      (node (ref "ISP_B") (pin "4") (pinfunction "4_4") (pintype "passive"))
      (node (ref "R53") (pin "2") (pinfunction "2_2") (pintype "passive"))
      (node (ref "U3") (pin "15") (pinfunction "PB3_15") (pintype "bidirectional"))
    )
    (net (code "19") (name "MUX_A") (class "Default")
      (node (ref "Q1") (pin "3") (pinfunction "D_3") (pintype "passive"))
      (node (ref "R7") (pin "1") (pinfunction "1_1") (pintype "passive"))
      (node (ref "U2") (pin "10") (pinfunction "A_10") (pintype "input"))
    )
    (net (code "20") (name "MUX_A_1") (class "Default")
      (node (ref "Q5") (pin "3") (pinfunction "D_3") (pintype "passive"))
      (node (ref "R58") (pin "1") (pinfunction "1_1") (pintype "passive"))
      (node (ref "U4") (pin "10") (pinfunction "A_10") (pintype "input"))
    )
    (net (code "21") (name "MUX_B") (class "Default")
      (node (ref "Q2") (pin "3") (pinfunction "D_3") (pintype "passive"))
      (node (ref "R8") (pin "1") (pinfunction "1_1") (pintype "passive"))
      (node (ref "U2") (pin "9") (pinfunction "B_9") (pintype "input"))
    )
    (net (code "22") (name "MUX_B_1") (class "Default")
      (node (ref "Q6") (pin "3") (pinfunction "D_3") (pintype "passive"))
      (node (ref "R59") (pin "1") (pinfunction "1_1") (pintype "passive"))
      (node (ref "U4") (pin "9") (pinfunction "B_9") (pintype "input"))
    )
    (net (code "23") (name "N$15") (class "Default")
      (node (ref "U1") (pin "2") (pinfunction "PD4_2") (pintype "bidirectional"))
      (node (ref "U7") (pin "3") (pinfunction "SCK_3") (pintype "input"))
    )
    (net (code "24") (name "N$15_1") (class "Default")
      (node (ref "U$7") (pin "3") (pinfunction "SCK_3") (pintype "input"))
      (node (ref "U3") (pin "2") (pinfunction "PD4_2") (pintype "bidirectional"))
    )
    (net (code "25") (name "N$16") (class "Default")
      (node (ref "U1") (pin "32") (pinfunction "PD2_32") (pintype "bidirectional"))
      (node (ref "U7") (pin "2") (pinfunction "~{CS}_2") (pintype "input"))
    )
    (net (code "26") (name "N$16_1") (class "Default")
      (node (ref "U$7") (pin "2") (pinfunction "~{CS}_2") (pintype "input"))
      (node (ref "U3") (pin "32") (pinfunction "PD2_32") (pintype "bidirectional"))
    )
    (net (code "27") (name "N$25") (class "Default")
      (node (ref "U1") (pin "31") (pinfunction "PD1_31") (pintype "bidirectional"))
      (node (ref "U7") (pin "4") (pinfunction "SDI_4") (pintype "input"))
    )
    (net (code "28") (name "N$25_1") (class "Default")
      (node (ref "U$7") (pin "4") (pinfunction "SDI_4") (pintype "input"))
      (node (ref "U3") (pin "31") (pinfunction "PD1_31") (pintype "bidirectional"))
    )
    (net (code "29") (name "Net-(C5-Pad1)") (class "Default")
      (node (ref "C5") (pin "1") (pinfunction "1_1") (pintype "passive"))
      (node (ref "R3") (pin "1") (pinfunction "1_1") (pintype "passive"))
    )
    (net (code "30") (name "Net-(C6-Pad1)") (class "Default")
      (node (ref "C6") (pin "1") (pinfunction "1_1") (pintype "passive"))
      (node (ref "R4") (pin "1") (pinfunction "1_1") (pintype "passive"))
    )
    (net (code "31") (name "Net-(C15-Pad1)") (class "Default")
      (node (ref "C15") (pin "1") (pinfunction "1_1") (pintype "passive"))
      (node (ref "R15") (pin "1") (pinfunction "1_1") (pintype "passive"))
    )
    (net (code "32") (name "Net-(C16-Pad1)") (class "Default")
      (node (ref "C16") (pin "1") (pinfunction "1_1") (pintype "passive"))
      (node (ref "R16") (pin "1") (pinfunction "1_1") (pintype "passive"))
    )
    (net (code "33") (name "Net-(C20-Pad-)") (class "Default")
      (node (ref "C20") (pin "-") (pinfunction "-_-") (pintype "passive"))
      (node (ref "R14") (pin "1") (pinfunction "1_1") (pintype "passive"))
    )
    (net (code "34") (name "Net-(C21-Pad-)") (class "Default")
      (node (ref "C21") (pin "-") (pinfunction "-_-") (pintype "passive"))
      (node (ref "R20") (pin "1") (pinfunction "1_1") (pintype "passive"))
    )
    (net (code "35") (name "Net-(C32-Pad1)") (class "Default")
      (node (ref "C32") (pin "1") (pinfunction "1_1") (pintype "passive"))
      (node (ref "R41") (pin "1") (pinfunction "1_1") (pintype "passive"))
    )
    (net (code "36") (name "Net-(C33-Pad1)") (class "Default")
      (node (ref "C33") (pin "1") (pinfunction "1_1") (pintype "passive"))
      (node (ref "R42") (pin "1") (pinfunction "1_1") (pintype "passive"))
    )
    (net (code "37") (name "Net-(C34-Pad1)") (class "Default")
      (node (ref "C34") (pin "1") (pinfunction "1_1") (pintype "passive"))
      (node (ref "R43") (pin "1") (pinfunction "1_1") (pintype "passive"))
    )
    (net (code "38") (name "Net-(C35-Pad1)") (class "Default")
      (node (ref "C35") (pin "1") (pinfunction "1_1") (pintype "passive"))
      (node (ref "R44") (pin "1") (pinfunction "1_1") (pintype "passive"))
    )
    (net (code "39") (name "Net-(C47-Pad-)") (class "Default")
      (node (ref "C47") (pin "-") (pinfunction "-_-") (pintype "passive"))
      (node (ref "R34") (pin "1") (pinfunction "1_1") (pintype "passive"))
    )
    (net (code "40") (name "Net-(C48-Pad-)") (class "Default")
      (node (ref "C48") (pin "-") (pinfunction "-_-") (pintype "passive"))
      (node (ref "R47") (pin "1") (pinfunction "1_1") (pintype "passive"))
    )
    (net (code "41") (name "Net-(IC1A--IN)") (class "Default")
      (node (ref "C19") (pin "1") (pinfunction "1_1") (pintype "passive"))
      (node (ref "IC1") (pin "2") (pinfunction "-IN_2") (pintype "input"))
      (node (ref "R10") (pin "2") (pinfunction "2_2") (pintype "passive"))
      (node (ref "R11") (pin "2") (pinfunction "2_2") (pintype "passive"))
      (node (ref "R9") (pin "1") (pinfunction "1_1") (pintype "passive"))
    )
    (net (code "42") (name "Net-(IC1B--IN)") (class "Default")
      (node (ref "C3") (pin "1") (pinfunction "1_1") (pintype "passive"))
      (node (ref "IC1") (pin "6") (pinfunction "-IN_6") (pintype "input"))
      (node (ref "IC2") (pin "4") (pinfunction "OUT_4") (pintype "output"))
      (node (ref "R1") (pin "1") (pinfunction "1_1") (pintype "passive"))
    )
    (net (code "43") (name "Net-(IC2A-CTRL)") (class "Default")
      (node (ref "C28") (pin "1") (pinfunction "1_1") (pintype "passive"))
      (node (ref "IC2") (pin "3") (pinfunction "CTRL_3") (pintype "input"))
      (node (ref "R30") (pin "2") (pinfunction "2_2") (pintype "passive"))
    )
    (net (code "44") (name "Net-(IC2A-IN)") (class "Default")
      (node (ref "IC2") (pin "2") (pinfunction "IN_2") (pintype "input"))
      (node (ref "R14") (pin "2") (pinfunction "2_2") (pintype "passive"))
      (node (ref "R15") (pin "2") (pinfunction "2_2") (pintype "passive"))
    )
    (net (code "45") (name "Net-(IC2B-IN)") (class "Default")
      (node (ref "IC2") (pin "7") (pinfunction "IN_7") (pintype "input"))
      (node (ref "R16") (pin "2") (pinfunction "2_2") (pintype "passive"))
      (node (ref "R17") (pin "2") (pinfunction "2_2") (pintype "passive"))
    )
    (net (code "46") (name "Net-(IC2B-OUT)") (class "Default")
      (node (ref "C12") (pin "1") (pinfunction "1_1") (pintype "passive"))
      (node (ref "IC2") (pin "5") (pinfunction "OUT_5") (pintype "output"))
      (node (ref "IC3") (pin "6") (pinfunction "-IN_6") (pintype "input"))
      (node (ref "Z5") (pin "2") (pinfunction "A_2") (pintype "bidirectional"))
    )
    (net (code "47") (name "Net-(IC2C-IN)") (class "Default")
      (node (ref "IC2") (pin "10") (pinfunction "IN_10") (pintype "input"))
      (node (ref "R4") (pin "2") (pinfunction "2_2") (pintype "passive"))
      (node (ref "R5") (pin "2") (pinfunction "2_2") (pintype "passive"))
    )
    (net (code "48") (name "Net-(IC2C-OUT)") (class "Default")
      (node (ref "C10") (pin "1") (pinfunction "1_1") (pintype "passive"))
      (node (ref "IC2") (pin "12") (pinfunction "OUT_12") (pintype "output"))
      (node (ref "IC3") (pin "9") (pinfunction "-IN_9") (pintype "input"))
    )
    (net (code "49") (name "Net-(IC2D-IN)") (class "Default")
      (node (ref "IC2") (pin "15") (pinfunction "IN_15") (pintype "input"))
      (node (ref "R2") (pin "1") (pinfunction "1_1") (pintype "passive"))
      (node (ref "R3") (pin "2") (pinfunction "2_2") (pintype "passive"))
    )
    (net (code "50") (name "Net-(IC2D-OUT)") (class "Default")
      (node (ref "IC2") (pin "13") (pinfunction "OUT_13") (pintype "output"))
      (node (ref "IC3") (pin "13") (pinfunction "-IN_13") (pintype "input"))
      (node (ref "R6") (pin "1") (pinfunction "1_1") (pintype "passive"))
    )
    (net (code "51") (name "Net-(IC3A--IN)") (class "Default")
      (node (ref "IC3") (pin "2") (pinfunction "-IN_2") (pintype "input"))
      (node (ref "R18") (pin "1") (pinfunction "1_1") (pintype "passive"))
      (node (ref "R19") (pin "1") (pinfunction "1_1") (pintype "passive"))
      (node (ref "R20") (pin "2") (pinfunction "2_2") (pintype "passive"))
      (node (ref "R21") (pin "1") (pinfunction "1_1") (pintype "passive"))
      (node (ref "R22") (pin "2") (pinfunction "2_2") (pintype "passive"))
    )
    (net (code "52") (name "Net-(IC3D-OUT)") (class "Default")
      (node (ref "IC3") (pin "14") (pinfunction "OUT_14") (pintype "output"))
      (node (ref "R19") (pin "2") (pinfunction "2_2") (pintype "passive"))
      (node (ref "R6") (pin "2") (pinfunction "2_2") (pintype "passive"))
    )
    (net (code "53") (name "Net-(IC4A-CTRL)") (class "Default")
      (node (ref "C56") (pin "1") (pinfunction "1_1") (pintype "passive"))
      (node (ref "IC4") (pin "3") (pinfunction "CTRL_3") (pintype "input"))
      (node (ref "R60") (pin "2") (pinfunction "2_2") (pintype "passive"))
    )
    (net (code "54") (name "Net-(IC4A-IN)") (class "Default")
      (node (ref "IC4") (pin "2") (pinfunction "IN_2") (pintype "input"))
      (node (ref "R44") (pin "2") (pinfunction "2_2") (pintype "passive"))
      (node (ref "R47") (pin "2") (pinfunction "2_2") (pintype "passive"))
    )
    (net (code "55") (name "Net-(IC4A-OUT)") (class "Default")
      (node (ref "C44") (pin "1") (pinfunction "1_1") (pintype "passive"))
      (node (ref "IC4") (pin "4") (pinfunction "OUT_4") (pintype "output"))
      (node (ref "IC6") (pin "6") (pinfunction "-IN_6") (pintype "input"))
      (node (ref "R52") (pin "1") (pinfunction "1_1") (pintype "passive"))
    )
    (net (code "56") (name "Net-(IC4B-IN)") (class "Default")
      (node (ref "IC4") (pin "7") (pinfunction "IN_7") (pintype "input"))
      (node (ref "R36") (pin "2") (pinfunction "2_2") (pintype "passive"))
      (node (ref "R43") (pin "2") (pinfunction "2_2") (pintype "passive"))
    )
    (net (code "57") (name "Net-(IC4B-OUT)") (class "Default")
      (node (ref "C30") (pin "1") (pinfunction "1_1") (pintype "passive"))
      (node (ref "IC4") (pin "5") (pinfunction "OUT_5") (pintype "output"))
      (node (ref "IC5") (pin "6") (pinfunction "-IN_6") (pintype "input"))
      (node (ref "Z3") (pin "2") (pinfunction "A_2") (pintype "bidirectional"))
    )
    (net (code "58") (name "Net-(IC4C-IN)") (class "Default")
      (node (ref "IC4") (pin "10") (pinfunction "IN_10") (pintype "input"))
      (node (ref "R39") (pin "2") (pinfunction "2_2") (pintype "passive"))
      (node (ref "R41") (pin "2") (pinfunction "2_2") (pintype "passive"))
    )
    (net (code "59") (name "Net-(IC4C-OUT)") (class "Default")
      (node (ref "C31") (pin "1") (pinfunction "1_1") (pintype "passive"))
      (node (ref "IC4") (pin "12") (pinfunction "OUT_12") (pintype "output"))
      (node (ref "IC5") (pin "9") (pinfunction "-IN_9") (pintype "input"))
    )
    (net (code "60") (name "Net-(IC4D-IN)") (class "Default")
      (node (ref "IC4") (pin "15") (pinfunction "IN_15") (pintype "input"))
      (node (ref "R37") (pin "1") (pinfunction "1_1") (pintype "passive"))
      (node (ref "R42") (pin "2") (pinfunction "2_2") (pintype "passive"))
    )
    (net (code "61") (name "Net-(IC4D-OUT)") (class "Default")
      (node (ref "IC4") (pin "13") (pinfunction "OUT_13") (pintype "output"))
      (node (ref "IC5") (pin "13") (pinfunction "-IN_13") (pintype "input"))
      (node (ref "R45") (pin "1") (pinfunction "1_1") (pintype "passive"))
    )
    (net (code "62") (name "Net-(IC5A--IN)") (class "Default")
      (node (ref "IC5") (pin "2") (pinfunction "-IN_2") (pintype "input"))
      (node (ref "R34") (pin "2") (pinfunction "2_2") (pintype "passive"))
      (node (ref "R35") (pin "1") (pinfunction "1_1") (pintype "passive"))
      (node (ref "R38") (pin "1") (pinfunction "1_1") (pintype "passive"))
      (node (ref "R40") (pin "1") (pinfunction "1_1") (pintype "passive"))
      (node (ref "R46") (pin "2") (pinfunction "2_2") (pintype "passive"))
    )
    (net (code "63") (name "Net-(IC5D-OUT)") (class "Default")
      (node (ref "IC5") (pin "14") (pinfunction "OUT_14") (pintype "output"))
      (node (ref "R38") (pin "2") (pinfunction "2_2") (pintype "passive"))
      (node (ref "R45") (pin "2") (pinfunction "2_2") (pintype "passive"))
    )
    (net (code "64") (name "Net-(IC6A--IN)") (class "Default")
      (node (ref "C29") (pin "1") (pinfunction "1_1") (pintype "passive"))
      (node (ref "IC6") (pin "2") (pinfunction "-IN_2") (pintype "input"))
      (node (ref "R31") (pin "1") (pinfunction "1_1") (pintype "passive"))
      (node (ref "R32") (pin "2") (pinfunction "2_2") (pintype "passive"))
      (node (ref "R57") (pin "2") (pinfunction "2_2") (pintype "passive"))
    )
    (net (code "65") (name "Net-(LED1-PadA)") (class "Default")
      (node (ref "LED1") (pin "A") (pinfunction "A_A") (pintype "passive"))
      (node (ref "R25") (pin "1") (pinfunction "1_1") (pintype "passive"))
    )
    (net (code "66") (name "Net-(LED2-PadA)") (class "Default")
      (node (ref "LED2") (pin "A") (pinfunction "A_A") (pintype "passive"))
      (node (ref "R26") (pin "1") (pinfunction "1_1") (pintype "passive"))
    )
    (net (code "67") (name "Net-(LED3-PadA)") (class "Default")
      (node (ref "LED3") (pin "A") (pinfunction "A_A") (pintype "passive"))
      (node (ref "R49") (pin "1") (pinfunction "1_1") (pintype "passive"))
    )
    (net (code "68") (name "Net-(LED4-PadA)") (class "Default")
      (node (ref "LED4") (pin "A") (pinfunction "A_A") (pintype "passive"))
      (node (ref "R50") (pin "1") (pinfunction "1_1") (pintype "passive"))
    )
    (net (code "69") (name "Net-(Q1-G)") (class "Default")
      (node (ref "Q1") (pin "1") (pinfunction "G_1") (pintype "passive"))
      (node (ref "U1") (pin "23") (pinfunction "PC0_23") (pintype "bidirectional"))
    )
    (net (code "70") (name "Net-(Q2-G)") (class "Default")
      (node (ref "Q2") (pin "1") (pinfunction "G_1") (pintype "passive"))
      (node (ref "U1") (pin "24") (pinfunction "PC1_24") (pintype "bidirectional"))
    )
    (net (code "71") (name "Net-(Q5-G)") (class "Default")
      (node (ref "Q5") (pin "1") (pinfunction "G_1") (pintype "passive"))
      (node (ref "U3") (pin "23") (pinfunction "PC0_23") (pintype "bidirectional"))
    )
    (net (code "72") (name "Net-(Q6-G)") (class "Default")
      (node (ref "Q6") (pin "1") (pinfunction "G_1") (pintype "passive"))
      (node (ref "U3") (pin "24") (pinfunction "PC1_24") (pintype "bidirectional"))
    )
    (net (code "73") (name "Net-(R23-E)") (class "Default")
      (node (ref "R10") (pin "1") (pinfunction "1_1") (pintype "passive"))
      (node (ref "R23") (pin "1") (pinfunction "E_1") (pintype "passive"))
      (node (ref "R23") (pin "2") (pinfunction "S_2") (pintype "passive"))
    )
    (net (code "74") (name "Net-(R33-E)") (class "Default")
      (node (ref "R32") (pin "1") (pinfunction "1_1") (pintype "passive"))
      (node (ref "R33") (pin "1") (pinfunction "E_1") (pintype "passive"))
      (node (ref "R33") (pin "2") (pinfunction "S_2") (pintype "passive"))
    )
    (net (code "75") (name "Net-(U1-PB6)") (class "Default")
      (node (ref "C25") (pin "2") (pinfunction "2_2") (pintype "passive"))
      (node (ref "Q3") (pin "2") (pinfunction "2_2") (pintype "passive"))
      (node (ref "U1") (pin "7") (pinfunction "PB6_7") (pintype "bidirectional"))
    )
    (net (code "76") (name "Net-(U1-PB7)") (class "Default")
      (node (ref "C26") (pin "2") (pinfunction "2_2") (pintype "passive"))
      (node (ref "Q3") (pin "1") (pinfunction "1_1") (pintype "passive"))
      (node (ref "U1") (pin "8") (pinfunction "PB7_8") (pintype "bidirectional"))
    )
    (net (code "77") (name "Net-(U1-PC4)") (class "Default")
      (node (ref "R25") (pin "2") (pinfunction "2_2") (pintype "passive"))
      (node (ref "U1") (pin "27") (pinfunction "PC4_27") (pintype "bidirectional"))
    )
    (net (code "78") (name "Net-(U1-PC5)") (class "Default")
      (node (ref "R26") (pin "2") (pinfunction "2_2") (pintype "passive"))
      (node (ref "U1") (pin "28") (pinfunction "PC5_28") (pintype "bidirectional"))
    )
    (net (code "79") (name "Net-(U1-PC6{slash}~{RESET})") (class "Default")
      (node (ref "ISP_A") (pin "5") (pinfunction "5_5") (pintype "passive"))
      (node (ref "R29") (pin "1") (pinfunction "1_1") (pintype "passive"))
      (node (ref "U1") (pin "29") (pinfunction "PC6/~{RESET}_29") (pintype "bidirectional"))
    )
    (net (code "80") (name "Net-(U2-X)") (class "Default")
      (node (ref "C20") (pin "+") (pinfunction "+_+") (pintype "passive"))
      (node (ref "U2") (pin "13") (pinfunction "X_13") (pintype "bidirectional"))
    )
    (net (code "81") (name "Net-(U3-PB6)") (class "Default")
      (node (ref "C36") (pin "2") (pinfunction "2_2") (pintype "passive"))
      (node (ref "Q4") (pin "2") (pinfunction "2_2") (pintype "passive"))
      (node (ref "U3") (pin "7") (pinfunction "PB6_7") (pintype "bidirectional"))
    )
    (net (code "82") (name "Net-(U3-PB7)") (class "Default")
      (node (ref "C37") (pin "2") (pinfunction "2_2") (pintype "passive"))
      (node (ref "Q4") (pin "1") (pinfunction "1_1") (pintype "passive"))
      (node (ref "U3") (pin "8") (pinfunction "PB7_8") (pintype "bidirectional"))
    )
    (net (code "83") (name "Net-(U3-PC4)") (class "Default")
      (node (ref "R49") (pin "2") (pinfunction "2_2") (pintype "passive"))
      (node (ref "U3") (pin "27") (pinfunction "PC4_27") (pintype "bidirectional"))
    )
    (net (code "84") (name "Net-(U3-PC5)") (class "Default")
      (node (ref "R50") (pin "2") (pinfunction "2_2") (pintype "passive"))
      (node (ref "U3") (pin "28") (pinfunction "PC5_28") (pintype "bidirectional"))
    )
    (net (code "85") (name "Net-(U3-PC6{slash}~{RESET})") (class "Default")
      (node (ref "ISP_B") (pin "5") (pinfunction "5_5") (pintype "passive"))
      (node (ref "R48") (pin "1") (pinfunction "1_1") (pintype "passive"))
      (node (ref "U3") (pin "29") (pinfunction "PC6/~{RESET}_29") (pintype "bidirectional"))
    )
    (net (code "86") (name "Net-(U4-X)") (class "Default")
      (node (ref "C48") (pin "+") (pinfunction "+_+") (pintype "passive"))
      (node (ref "U4") (pin "13") (pinfunction "X_13") (pintype "bidirectional"))
    )
    (net (code "87") (name "Net-(Z1-A)") (class "Default")
      (node (ref "R11") (pin "1") (pinfunction "1_1") (pintype "passive"))
      (node (ref "R12") (pin "2") (pinfunction "2_2") (pintype "passive"))
      (node (ref "Z1") (pin "2") (pinfunction "A_2") (pintype "bidirectional"))
    )
    (net (code "88") (name "Net-(Z2-A)") (class "Default")
      (node (ref "R56") (pin "2") (pinfunction "2_2") (pintype "passive"))
      (node (ref "R57") (pin "1") (pinfunction "1_1") (pintype "passive"))
      (node (ref "Z2") (pin "2") (pinfunction "A_2") (pintype "bidirectional"))
    )
    (net (code "89") (name "Net-(Z3-K)") (class "Default")
      (node (ref "Z3") (pin "1") (pinfunction "K_1") (pintype "bidirectional"))
      (node (ref "Z4") (pin "1") (pinfunction "K_1") (pintype "bidirectional"))
    )
    (net (code "90") (name "Net-(Z5-K)") (class "Default")
      (node (ref "Z5") (pin "1") (pinfunction "K_1") (pintype "bidirectional"))
      (node (ref "Z6") (pin "1") (pinfunction "K_1") (pintype "bidirectional"))
    )
    (net (code "91") (name "OSC") (class "Default")
      (node (ref "C21") (pin "+") (pinfunction "+_+") (pintype "passive"))
      (node (ref "U7") (pin "6") (pinfunction "~{VOUTB}_6") (pintype "input"))
    )
    (net (code "92") (name "OSC_1") (class "Default")
      (node (ref "C47") (pin "+") (pinfunction "+_+") (pintype "passive"))
      (node (ref "U$7") (pin "6") (pinfunction "~{VOUTB}_6") (pintype "input"))
    )
    (net (code "93") (name "OUT") (class "Default")
      (node (ref "C3") (pin "2") (pinfunction "2_2") (pintype "passive"))
      (node (ref "IC1") (pin "7") (pinfunction "OUT_7") (pintype "output"))
      (node (ref "R1") (pin "2") (pinfunction "2_2") (pintype "passive"))
      (node (ref "R64") (pin "2") (pinfunction "2_2") (pintype "passive"))
    )
    (net (code "94") (name "OUTA") (class "Default")
      (node (ref "JP2") (pin "6") (pinfunction "6_6") (pintype "passive"))
      (node (ref "R64") (pin "1") (pinfunction "1_1") (pintype "passive"))
    )
    (net (code "95") (name "OUTB") (class "Default")
      (node (ref "JP2") (pin "5") (pinfunction "5_5") (pintype "passive"))
      (node (ref "R62") (pin "1") (pinfunction "1_1") (pintype "passive"))
    )
    (net (code "96") (name "OUT_1") (class "Default")
      (node (ref "C44") (pin "2") (pinfunction "2_2") (pintype "passive"))
      (node (ref "IC6") (pin "7") (pinfunction "OUT_7") (pintype "output"))
      (node (ref "R52") (pin "2") (pinfunction "2_2") (pintype "passive"))
      (node (ref "R62") (pin "2") (pinfunction "2_2") (pintype "passive"))
    )
    (net (code "97") (name "RES_CONTROL") (class "Default")
      (node (ref "C14") (pin "1") (pinfunction "1_1") (pintype "passive"))
      (node (ref "IC2") (pin "14") (pinfunction "CTRL_14") (pintype "input"))
      (node (ref "R13") (pin "2") (pinfunction "2_2") (pintype "passive"))
    )
    (net (code "98") (name "RES_CONTROL_1") (class "Default")
      (node (ref "C40") (pin "1") (pinfunction "1_1") (pintype "passive"))
      (node (ref "IC4") (pin "14") (pinfunction "CTRL_14") (pintype "input"))
      (node (ref "R51") (pin "2") (pinfunction "2_2") (pintype "passive"))
    )
    (net (code "99") (name "RES_PWM") (class "Default")
      (node (ref "R13") (pin "1") (pinfunction "1_1") (pintype "passive"))
      (node (ref "U1") (pin "9") (pinfunction "PD5_9") (pintype "bidirectional"))
    )
    (net (code "100") (name "RES_PWM_1") (class "Default")
      (node (ref "R51") (pin "1") (pinfunction "1_1") (pintype "passive"))
      (node (ref "U3") (pin "9") (pinfunction "PD5_9") (pintype "bidirectional"))
    )
    (net (code "101") (name "SC") (class "Default")
      (node (ref "JP4") (pin "2") (pinfunction "2_2") (pintype "passive"))
      (node (ref "R28") (pin "1") (pinfunction "1_1") (pintype "passive"))
      (node (ref "R55") (pin "1") (pinfunction "1_1") (pintype "passive"))
    )
    (net (code "102") (name "SCK") (class "Default")
      (node (ref "ISP_A") (pin "3") (pinfunction "3_3") (pintype "passive"))
      (node (ref "R28") (pin "2") (pinfunction "2_2") (pintype "passive"))
      (node (ref "U1") (pin "17") (pinfunction "PB5_17") (pintype "bidirectional"))
    )
    (net (code "103") (name "SCK_1") (class "Default")
      (node (ref "ISP_B") (pin "3") (pinfunction "3_3") (pintype "passive"))
      (node (ref "R55") (pin "2") (pinfunction "2_2") (pintype "passive"))
      (node (ref "U3") (pin "17") (pinfunction "PB5_17") (pintype "bidirectional"))
    )
    (net (code "104") (name "SS") (class "Default")
      (node (ref "R63") (pin "2") (pinfunction "2_2") (pintype "passive"))
      (node (ref "U1") (pin "14") (pinfunction "PB2_14") (pintype "bidirectional"))
    )
    (net (code "105") (name "SSA") (class "Default")
      (node (ref "JP4") (pin "6") (pinfunction "6_6") (pintype "passive"))
      (node (ref "R63") (pin "1") (pinfunction "1_1") (pintype "passive"))
    )
    (net (code "106") (name "SSB") (class "Default")
      (node (ref "JP4") (pin "5") (pinfunction "5_5") (pintype "passive"))
      (node (ref "R61") (pin "1") (pinfunction "1_1") (pintype "passive"))
    )
    (net (code "107") (name "SS_1") (class "Default")
      (node (ref "R61") (pin "2") (pinfunction "2_2") (pintype "passive"))
      (node (ref "U3") (pin "14") (pinfunction "PB2_14") (pintype "bidirectional"))
    )
    (net (code "108") (name "VCA_CONTROL") (class "Default")
      (node (ref "R30") (pin "1") (pinfunction "1_1") (pintype "passive"))
      (node (ref "U7") (pin "8") (pinfunction "VOUTA_8") (pintype "output"))
    )
    (net (code "109") (name "VCA_CONTROL_1") (class "Default")
      (node (ref "R60") (pin "1") (pinfunction "1_1") (pintype "passive"))
      (node (ref "U$7") (pin "8") (pinfunction "VOUTA_8") (pintype "output"))
    )
    (net (code "110") (name "VCC") (class "Default")
      (node (ref "C11") (pin "+") (pinfunction "+_+") (pintype "passive"))
      (node (ref "C17") (pin "1") (pinfunction "1_1") (pintype "passive"))
      (node (ref "C2") (pin "1") (pinfunction "1_1") (pintype "passive"))
      (node (ref "C4") (pin "1") (pinfunction "1_1") (pintype "passive"))
      (node (ref "C41") (pin "1") (pinfunction "1_1") (pintype "passive"))
      (node (ref "C42") (pin "1") (pinfunction "1_1") (pintype "passive"))
      (node (ref "C43") (pin "1") (pinfunction "1_1") (pintype "passive"))
      (node (ref "C53") (pin "+") (pinfunction "+_+") (pintype "passive"))
      (node (ref "C55") (pin "1") (pinfunction "1_1") (pintype "passive"))
      (node (ref "C9") (pin "1") (pinfunction "1_1") (pintype "passive"))
      (node (ref "IC1") (pin "8") (pinfunction "V+_8") (pintype "power_in"))
      (node (ref "IC2") (pin "16") (pinfunction "V+_16") (pintype "power_in"))
      (node (ref "IC3") (pin "4") (pinfunction "V+_4") (pintype "power_in"))
      (node (ref "IC4") (pin "16") (pinfunction "V+_16") (pintype "power_in"))
      (node (ref "IC5") (pin "4") (pinfunction "V+_4") (pintype "power_in"))
      (node (ref "IC6") (pin "8") (pinfunction "V+_8") (pintype "power_in"))
      (node (ref "JP2") (pin "4") (pinfunction "4_4") (pintype "passive"))
      (node (ref "R58") (pin "2") (pinfunction "2_2") (pintype "passive"))
      (node (ref "R59") (pin "2") (pinfunction "2_2") (pintype "passive"))
      (node (ref "R7") (pin "2") (pinfunction "2_2") (pintype "passive"))
      (node (ref "R8") (pin "2") (pinfunction "2_2") (pintype "passive"))
      (node (ref "U2") (pin "16") (pinfunction "VDD_16") (pintype "input"))
      (node (ref "U4") (pin "16") (pinfunction "VDD_16") (pintype "input"))
    )
    (net (code "111") (name "VEE") (class "Default")
      (node (ref "C1") (pin "-") (pinfunction "-_-") (pintype "passive"))
      (node (ref "C13") (pin "2") (pinfunction "2_2") (pintype "passive"))
      (node (ref "C18") (pin "2") (pinfunction "2_2") (pintype "passive"))
      (node (ref "C49") (pin "2") (pinfunction "2_2") (pintype "passive"))
      (node (ref "C50") (pin "2") (pinfunction "2_2") (pintype "passive"))
      (node (ref "C51") (pin "2") (pinfunction "2_2") (pintype "passive"))
      (node (ref "C52") (pin "2") (pinfunction "2_2") (pintype "passive"))
      (node (ref "C54") (pin "-") (pinfunction "-_-") (pintype "passive"))
      (node (ref "C7") (pin "2") (pinfunction "2_2") (pintype "passive"))
      (node (ref "C8") (pin "2") (pinfunction "2_2") (pintype "passive"))
      (node (ref "IC1") (pin "4") (pinfunction "V-_4") (pintype "power_in"))
      (node (ref "IC2") (pin "9") (pinfunction "V-_9") (pintype "power_in"))
      (node (ref "IC3") (pin "11") (pinfunction "V-_11") (pintype "power_in"))
      (node (ref "IC4") (pin "9") (pinfunction "V-_9") (pintype "power_in"))
      (node (ref "IC5") (pin "11") (pinfunction "V-_11") (pintype "power_in"))
      (node (ref "IC6") (pin "4") (pinfunction "V-_4") (pintype "power_in"))
      (node (ref "JP2") (pin "2") (pinfunction "2_2") (pintype "passive"))
      (node (ref "R12") (pin "1") (pinfunction "1_1") (pintype "passive"))
      (node (ref "R56") (pin "1") (pinfunction "1_1") (pintype "passive"))
      (node (ref "U2") (pin "7") (pinfunction "VEE_7") (pintype "power_in"))
      (node (ref "U4") (pin "7") (pinfunction "VEE_7") (pintype "power_in"))
    )
    (net (code "112") (name "unconnected-(IC2E-MODE-Pad1)") (class "Default")
      (node (ref "IC2") (pin "1") (pinfunction "MODE_1") (pintype "input"))
    )
    (net (code "113") (name "unconnected-(IC4E-MODE-Pad1)") (class "Default")
      (node (ref "IC4") (pin "1") (pinfunction "MODE_1") (pintype "input"))
    )
    (net (code "114") (name "unconnected-(U1-ADC6-Pad19)") (class "Default")
      (node (ref "U1") (pin "19") (pinfunction "ADC6_19") (pintype "bidirectional"))
    )
    (net (code "115") (name "unconnected-(U1-ADC7-Pad22)") (class "Default")
      (node (ref "U1") (pin "22") (pinfunction "ADC7_22") (pintype "bidirectional"))
    )
    (net (code "116") (name "unconnected-(U1-AREF-Pad20)") (class "Default")
      (node (ref "U1") (pin "20") (pinfunction "AREF_20") (pintype "input"))
    )
    (net (code "117") (name "unconnected-(U1-PB1-Pad13)") (class "Default")
      (node (ref "U1") (pin "13") (pinfunction "PB1_13") (pintype "bidirectional"))
    )
    (net (code "118") (name "unconnected-(U1-PC2-Pad25)") (class "Default")
      (node (ref "U1") (pin "25") (pinfunction "PC2_25") (pintype "bidirectional"))
    )
    (net (code "119") (name "unconnected-(U1-PC3-Pad26)") (class "Default")
      (node (ref "U1") (pin "26") (pinfunction "PC3_26") (pintype "bidirectional"))
    )
    (net (code "120") (name "unconnected-(U1-PD0-Pad30)") (class "Default")
      (node (ref "U1") (pin "30") (pinfunction "PD0_30") (pintype "bidirectional"))
    )
    (net (code "121") (name "unconnected-(U1-PD3-Pad1)") (class "Default")
      (node (ref "U1") (pin "1") (pinfunction "PD3_1") (pintype "bidirectional"))
    )
    (net (code "122") (name "unconnected-(U1-PD7-Pad11)") (class "Default")
      (node (ref "U1") (pin "11") (pinfunction "PD7_11") (pintype "bidirectional"))
    )
    (net (code "123") (name "unconnected-(U2-Y-Pad3)") (class "Default")
      (node (ref "U2") (pin "3") (pinfunction "Y_3") (pintype "bidirectional"))
    )
    (net (code "124") (name "unconnected-(U3-ADC6-Pad19)") (class "Default")
      (node (ref "U3") (pin "19") (pinfunction "ADC6_19") (pintype "bidirectional"))
    )
    (net (code "125") (name "unconnected-(U3-ADC7-Pad22)") (class "Default")
      (node (ref "U3") (pin "22") (pinfunction "ADC7_22") (pintype "bidirectional"))
    )
    (net (code "126") (name "unconnected-(U3-AREF-Pad20)") (class "Default")
      (node (ref "U3") (pin "20") (pinfunction "AREF_20") (pintype "input"))
    )
    (net (code "127") (name "unconnected-(U3-PB1-Pad13)") (class "Default")
      (node (ref "U3") (pin "13") (pinfunction "PB1_13") (pintype "bidirectional"))
    )
    (net (code "128") (name "unconnected-(U3-PC2-Pad25)") (class "Default")
      (node (ref "U3") (pin "25") (pinfunction "PC2_25") (pintype "bidirectional"))
    )
    (net (code "129") (name "unconnected-(U3-PC3-Pad26)") (class "Default")
      (node (ref "U3") (pin "26") (pinfunction "PC3_26") (pintype "bidirectional"))
    )
    (net (code "130") (name "unconnected-(U3-PD0-Pad30)") (class "Default")
      (node (ref "U3") (pin "30") (pinfunction "PD0_30") (pintype "bidirectional"))
    )
    (net (code "131") (name "unconnected-(U3-PD3-Pad1)") (class "Default")
      (node (ref "U3") (pin "1") (pinfunction "PD3_1") (pintype "bidirectional"))
    )
    (net (code "132") (name "unconnected-(U3-PD7-Pad11)") (class "Default")
      (node (ref "U3") (pin "11") (pinfunction "PD7_11") (pintype "bidirectional"))
    )
    (net (code "133") (name "unconnected-(U4-Y-Pad3)") (class "Default")
      (node (ref "U4") (pin "3") (pinfunction "Y_3") (pintype "bidirectional"))
    )
  )
)
